# SH6_-_SCIENCE_CONTROLS.net
KiCad netlist of a schematic drawn in Altium Designer
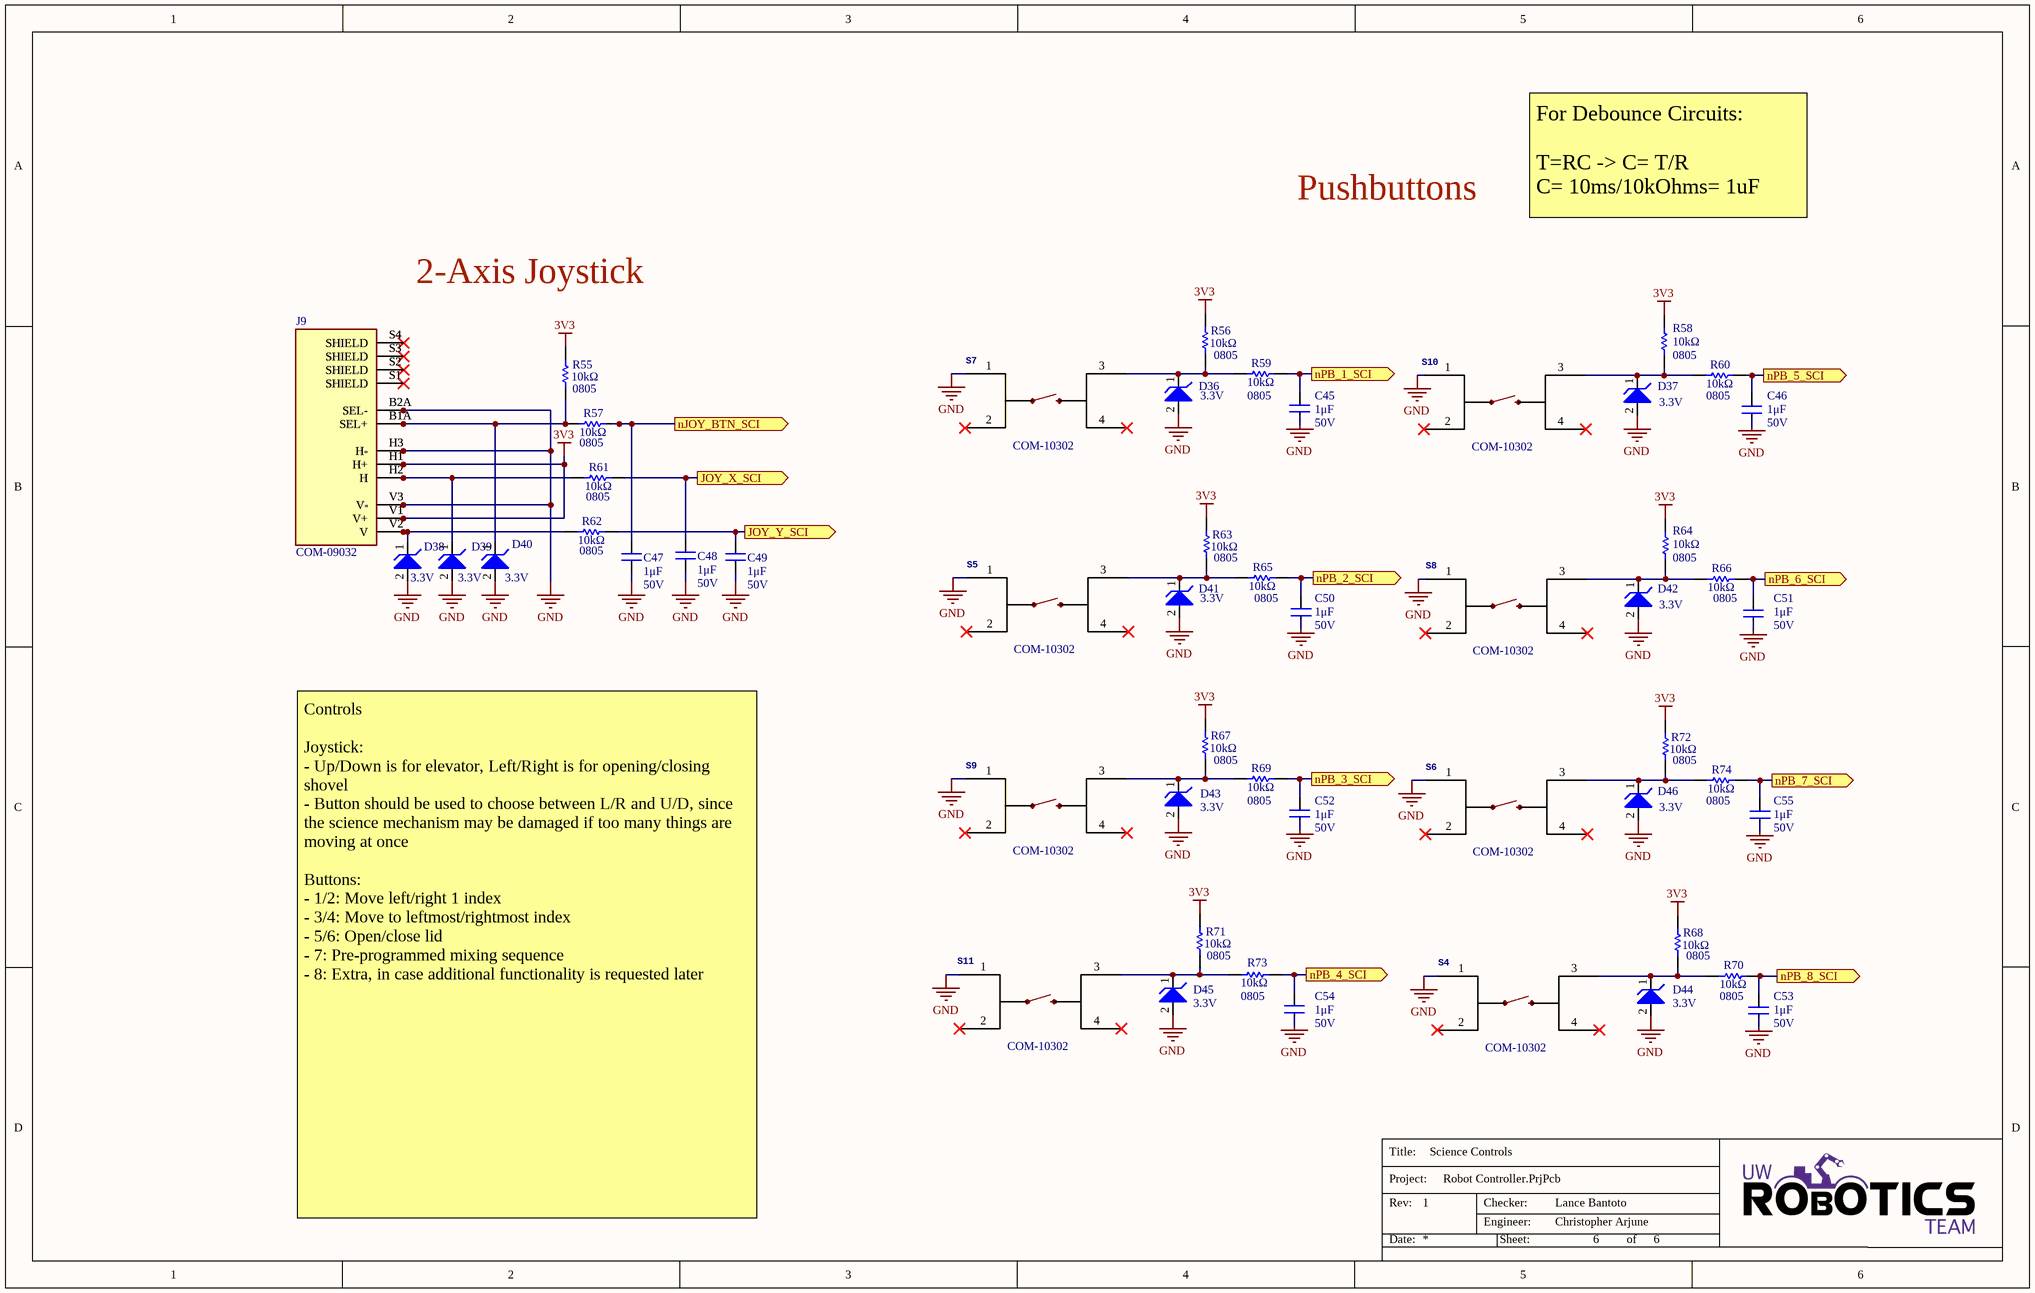
[diagram p0: SH6 - SCIENCE CONTROLS.SchDoc]

(export (version "E")
  (design (tool "Eeschema 10.0.6"))
  (components
    (comp (ref "C45")
      (value "1μF")
      (footprint "CAP2012")
      (description "CAP CER 1UF 50V X7R 0805")
      (fields
        (field (name "VOLTAGE RATING") "50V")
        (field (name "LCSC PART #") "C28323")
        (field (name "Comment") "CAP_1uF_50V_0805")
      )
      (libsource (lib "UWRT_Schematic_Library_2020") (part "CAP_1uF_50V_0805"))
    )
    (comp (ref "C46")
      (value "1μF")
      (footprint "CAP2012")
      (description "CAP CER 1UF 50V X7R 0805")
      (fields
        (field (name "VOLTAGE RATING") "50V")
        (field (name "LCSC PART #") "C28323")
        (field (name "Comment") "CAP_1uF_50V_0805")
      )
      (libsource (lib "UWRT_Schematic_Library_2020") (part "CAP_1uF_50V_0805"))
    )
    (comp (ref "C47")
      (value "1μF")
      (footprint "CAP2012")
      (description "CAP CER 1UF 50V X7R 0805")
      (fields
        (field (name "VOLTAGE RATING") "50V")
        (field (name "LCSC PART #") "C28323")
        (field (name "Comment") "CAP_1uF_50V_0805")
      )
      (libsource (lib "UWRT_Schematic_Library_2020") (part "CAP_1uF_50V_0805"))
    )
    (comp (ref "C48")
      (value "1μF")
      (footprint "CAP2012")
      (description "CAP CER 1UF 50V X7R 0805")
      (fields
        (field (name "VOLTAGE RATING") "50V")
        (field (name "LCSC PART #") "C28323")
        (field (name "Comment") "CAP_1uF_50V_0805")
      )
      (libsource (lib "UWRT_Schematic_Library_2020") (part "CAP_1uF_50V_0805"))
    )
    (comp (ref "C49")
      (value "1μF")
      (footprint "CAP2012")
      (description "CAP CER 1UF 50V X7R 0805")
      (fields
        (field (name "VOLTAGE RATING") "50V")
        (field (name "LCSC PART #") "C28323")
        (field (name "Comment") "CAP_1uF_50V_0805")
      )
      (libsource (lib "UWRT_Schematic_Library_2020") (part "CAP_1uF_50V_0805"))
    )
    (comp (ref "C50")
      (value "1μF")
      (footprint "CAP2012")
      (description "CAP CER 1UF 50V X7R 0805")
      (fields
        (field (name "VOLTAGE RATING") "50V")
        (field (name "LCSC PART #") "C28323")
        (field (name "Comment") "CAP_1uF_50V_0805")
      )
      (libsource (lib "UWRT_Schematic_Library_2020") (part "CAP_1uF_50V_0805"))
    )
    (comp (ref "C51")
      (value "1μF")
      (footprint "CAP2012")
      (description "CAP CER 1UF 50V X7R 0805")
      (fields
        (field (name "VOLTAGE RATING") "50V")
        (field (name "LCSC PART #") "C28323")
        (field (name "Comment") "CAP_1uF_50V_0805")
      )
      (libsource (lib "UWRT_Schematic_Library_2020") (part "CAP_1uF_50V_0805"))
    )
    (comp (ref "C52")
      (value "1μF")
      (footprint "CAP2012")
      (description "CAP CER 1UF 50V X7R 0805")
      (fields
        (field (name "VOLTAGE RATING") "50V")
        (field (name "LCSC PART #") "C28323")
        (field (name "Comment") "CAP_1uF_50V_0805")
      )
      (libsource (lib "UWRT_Schematic_Library_2020") (part "CAP_1uF_50V_0805"))
    )
    (comp (ref "C53")
      (value "1μF")
      (footprint "CAP2012")
      (description "CAP CER 1UF 50V X7R 0805")
      (fields
        (field (name "VOLTAGE RATING") "50V")
        (field (name "LCSC PART #") "C28323")
        (field (name "Comment") "CAP_1uF_50V_0805")
      )
      (libsource (lib "UWRT_Schematic_Library_2020") (part "CAP_1uF_50V_0805"))
    )
    (comp (ref "C54")
      (value "1μF")
      (footprint "CAP2012")
      (description "CAP CER 1UF 50V X7R 0805")
      (fields
        (field (name "VOLTAGE RATING") "50V")
        (field (name "LCSC PART #") "C28323")
        (field (name "Comment") "CAP_1uF_50V_0805")
      )
      (libsource (lib "UWRT_Schematic_Library_2020") (part "CAP_1uF_50V_0805"))
    )
    (comp (ref "C55")
      (value "1μF")
      (footprint "CAP2012")
      (description "CAP CER 1UF 50V X7R 0805")
      (fields
        (field (name "VOLTAGE RATING") "50V")
        (field (name "LCSC PART #") "C28323")
        (field (name "Comment") "CAP_1uF_50V_0805")
      )
      (libsource (lib "UWRT_Schematic_Library_2020") (part "CAP_1uF_50V_0805"))
    )
    (comp (ref "D36")
      (value "TVS_DIODE_UNIDIR_3.3V")
      (description "TVS DIODE 3.3V 14.1V SOD523")
      (fields (field (name "LCSC PART #") "C61148") (field (name "VOLTAGE - REVERSE STANDOFF (TYP)") "3.3V"))
      (libsource (lib "UWRT_Schematic_Library_2020") (part "TVS_DIODE_UNIDIR_3.3V"))
    )
    (comp (ref "D37")
      (value "TVS_DIODE_UNIDIR_3.3V")
      (description "TVS DIODE 3.3V 14.1V SOD523")
      (fields (field (name "LCSC PART #") "C61148") (field (name "VOLTAGE - REVERSE STANDOFF (TYP)") "3.3V"))
      (libsource (lib "UWRT_Schematic_Library_2020") (part "TVS_DIODE_UNIDIR_3.3V"))
    )
    (comp (ref "D38")
      (value "TVS_DIODE_UNIDIR_3.3V")
      (description "TVS DIODE 3.3V 14.1V SOD523")
      (fields (field (name "LCSC PART #") "C61148") (field (name "VOLTAGE - REVERSE STANDOFF (TYP)") "3.3V"))
      (libsource (lib "UWRT_Schematic_Library_2020") (part "TVS_DIODE_UNIDIR_3.3V"))
    )
    (comp (ref "D39")
      (value "TVS_DIODE_UNIDIR_3.3V")
      (description "TVS DIODE 3.3V 14.1V SOD523")
      (fields (field (name "LCSC PART #") "C61148") (field (name "VOLTAGE - REVERSE STANDOFF (TYP)") "3.3V"))
      (libsource (lib "UWRT_Schematic_Library_2020") (part "TVS_DIODE_UNIDIR_3.3V"))
    )
    (comp (ref "D40")
      (value "TVS_DIODE_UNIDIR_3.3V")
      (description "TVS DIODE 3.3V 14.1V SOD523")
      (fields (field (name "LCSC PART #") "C61148") (field (name "VOLTAGE - REVERSE STANDOFF (TYP)") "3.3V"))
      (libsource (lib "UWRT_Schematic_Library_2020") (part "TVS_DIODE_UNIDIR_3.3V"))
    )
    (comp (ref "D41")
      (value "TVS_DIODE_UNIDIR_3.3V")
      (description "TVS DIODE 3.3V 14.1V SOD523")
      (fields (field (name "LCSC PART #") "C61148") (field (name "VOLTAGE - REVERSE STANDOFF (TYP)") "3.3V"))
      (libsource (lib "UWRT_Schematic_Library_2020") (part "TVS_DIODE_UNIDIR_3.3V"))
    )
    (comp (ref "D42")
      (value "TVS_DIODE_UNIDIR_3.3V")
      (description "TVS DIODE 3.3V 14.1V SOD523")
      (fields (field (name "LCSC PART #") "C61148") (field (name "VOLTAGE - REVERSE STANDOFF (TYP)") "3.3V"))
      (libsource (lib "UWRT_Schematic_Library_2020") (part "TVS_DIODE_UNIDIR_3.3V"))
    )
    (comp (ref "D43")
      (value "TVS_DIODE_UNIDIR_3.3V")
      (description "TVS DIODE 3.3V 14.1V SOD523")
      (fields (field (name "LCSC PART #") "C61148") (field (name "VOLTAGE - REVERSE STANDOFF (TYP)") "3.3V"))
      (libsource (lib "UWRT_Schematic_Library_2020") (part "TVS_DIODE_UNIDIR_3.3V"))
    )
    (comp (ref "D44")
      (value "TVS_DIODE_UNIDIR_3.3V")
      (description "TVS DIODE 3.3V 14.1V SOD523")
      (fields (field (name "LCSC PART #") "C61148") (field (name "VOLTAGE - REVERSE STANDOFF (TYP)") "3.3V"))
      (libsource (lib "UWRT_Schematic_Library_2020") (part "TVS_DIODE_UNIDIR_3.3V"))
    )
    (comp (ref "D45")
      (value "TVS_DIODE_UNIDIR_3.3V")
      (description "TVS DIODE 3.3V 14.1V SOD523")
      (fields (field (name "LCSC PART #") "C61148") (field (name "VOLTAGE - REVERSE STANDOFF (TYP)") "3.3V"))
      (libsource (lib "UWRT_Schematic_Library_2020") (part "TVS_DIODE_UNIDIR_3.3V"))
    )
    (comp (ref "D46")
      (value "TVS_DIODE_UNIDIR_3.3V")
      (description "TVS DIODE 3.3V 14.1V SOD523")
      (fields (field (name "LCSC PART #") "C61148") (field (name "VOLTAGE - REVERSE STANDOFF (TYP)") "3.3V"))
      (libsource (lib "UWRT_Schematic_Library_2020") (part "TVS_DIODE_UNIDIR_3.3V"))
    )
    (comp (ref "J9")
      (value "2_AXIS_JOYSTICK")
      (footprint "2_AXIS_JOYSTICK")
      (description "JOYSTICK 10K OHM 2 AXIS TH")
      (fields (field (name "MANUFACTURER PART NUMBER 1") "COM-09032"))
      (libsource (lib "UWRT_Schematic_Library_2020") (part "2_AXIS_JOYSTICK"))
    )
    (comp (ref "R55")
      (value "10kΩ")
      (footprint "RESC0805")
      (description "RES 10K OHM 5% 1/8W 0805")
      (fields
        (field (name "LCSC PART #") "C17414")
        (field (name "PACKAGE/FOOTPRINT") "0805")
        (field (name "Comment") "RES_10kΩ_0805_5%")
      )
      (libsource (lib "UWRT_Schematic_Library_2020") (part "RES_10kΩ_0805_5%"))
    )
    (comp (ref "R56")
      (value "10kΩ")
      (footprint "RESC0805")
      (description "RES 10K OHM 5% 1/8W 0805")
      (fields
        (field (name "LCSC PART #") "C17414")
        (field (name "PACKAGE/FOOTPRINT") "0805")
        (field (name "Comment") "RES_10kΩ_0805_5%")
      )
      (libsource (lib "UWRT_Schematic_Library_2020") (part "RES_10kΩ_0805_5%"))
    )
    (comp (ref "R57")
      (value "10kΩ")
      (footprint "RESC0805")
      (description "RES 10K OHM 5% 1/8W 0805")
      (fields
        (field (name "LCSC PART #") "C17414")
        (field (name "PACKAGE/FOOTPRINT") "0805")
        (field (name "Comment") "RES_10kΩ_0805_5%")
      )
      (libsource (lib "UWRT_Schematic_Library_2020") (part "RES_10kΩ_0805_5%"))
    )
    (comp (ref "R58")
      (value "10kΩ")
      (footprint "RESC0805")
      (description "RES 10K OHM 5% 1/8W 0805")
      (fields
        (field (name "LCSC PART #") "C17414")
        (field (name "PACKAGE/FOOTPRINT") "0805")
        (field (name "Comment") "RES_10kΩ_0805_5%")
      )
      (libsource (lib "UWRT_Schematic_Library_2020") (part "RES_10kΩ_0805_5%"))
    )
    (comp (ref "R59")
      (value "10kΩ")
      (footprint "RESC0805")
      (description "RES 10K OHM 5% 1/8W 0805")
      (fields
        (field (name "LCSC PART #") "C17414")
        (field (name "PACKAGE/FOOTPRINT") "0805")
        (field (name "Comment") "RES_10kΩ_0805_5%")
      )
      (libsource (lib "UWRT_Schematic_Library_2020") (part "RES_10kΩ_0805_5%"))
    )
    (comp (ref "R60")
      (value "10kΩ")
      (footprint "RESC0805")
      (description "RES 10K OHM 5% 1/8W 0805")
      (fields
        (field (name "LCSC PART #") "C17414")
        (field (name "PACKAGE/FOOTPRINT") "0805")
        (field (name "Comment") "RES_10kΩ_0805_5%")
      )
      (libsource (lib "UWRT_Schematic_Library_2020") (part "RES_10kΩ_0805_5%"))
    )
    (comp (ref "R61")
      (value "10kΩ")
      (footprint "RESC0805")
      (description "RES 10K OHM 5% 1/8W 0805")
      (fields
        (field (name "LCSC PART #") "C17414")
        (field (name "PACKAGE/FOOTPRINT") "0805")
        (field (name "Comment") "RES_10kΩ_0805_5%")
      )
      (libsource (lib "UWRT_Schematic_Library_2020") (part "RES_10kΩ_0805_5%"))
    )
    (comp (ref "R62")
      (value "10kΩ")
      (footprint "RESC0805")
      (description "RES 10K OHM 5% 1/8W 0805")
      (fields
        (field (name "LCSC PART #") "C17414")
        (field (name "PACKAGE/FOOTPRINT") "0805")
        (field (name "Comment") "RES_10kΩ_0805_5%")
      )
      (libsource (lib "UWRT_Schematic_Library_2020") (part "RES_10kΩ_0805_5%"))
    )
    (comp (ref "R63")
      (value "10kΩ")
      (footprint "RESC0805")
      (description "RES 10K OHM 5% 1/8W 0805")
      (fields
        (field (name "LCSC PART #") "C17414")
        (field (name "PACKAGE/FOOTPRINT") "0805")
        (field (name "Comment") "RES_10kΩ_0805_5%")
      )
      (libsource (lib "UWRT_Schematic_Library_2020") (part "RES_10kΩ_0805_5%"))
    )
    (comp (ref "R64")
      (value "10kΩ")
      (footprint "RESC0805")
      (description "RES 10K OHM 5% 1/8W 0805")
      (fields
        (field (name "LCSC PART #") "C17414")
        (field (name "PACKAGE/FOOTPRINT") "0805")
        (field (name "Comment") "RES_10kΩ_0805_5%")
      )
      (libsource (lib "UWRT_Schematic_Library_2020") (part "RES_10kΩ_0805_5%"))
    )
    (comp (ref "R65")
      (value "10kΩ")
      (footprint "RESC0805")
      (description "RES 10K OHM 5% 1/8W 0805")
      (fields
        (field (name "LCSC PART #") "C17414")
        (field (name "PACKAGE/FOOTPRINT") "0805")
        (field (name "Comment") "RES_10kΩ_0805_5%")
      )
      (libsource (lib "UWRT_Schematic_Library_2020") (part "RES_10kΩ_0805_5%"))
    )
    (comp (ref "R66")
      (value "10kΩ")
      (footprint "RESC0805")
      (description "RES 10K OHM 5% 1/8W 0805")
      (fields
        (field (name "LCSC PART #") "C17414")
        (field (name "PACKAGE/FOOTPRINT") "0805")
        (field (name "Comment") "RES_10kΩ_0805_5%")
      )
      (libsource (lib "UWRT_Schematic_Library_2020") (part "RES_10kΩ_0805_5%"))
    )
    (comp (ref "R67")
      (value "10kΩ")
      (footprint "RESC0805")
      (description "RES 10K OHM 5% 1/8W 0805")
      (fields
        (field (name "LCSC PART #") "C17414")
        (field (name "PACKAGE/FOOTPRINT") "0805")
        (field (name "Comment") "RES_10kΩ_0805_5%")
      )
      (libsource (lib "UWRT_Schematic_Library_2020") (part "RES_10kΩ_0805_5%"))
    )
    (comp (ref "R68")
      (value "10kΩ")
      (footprint "RESC0805")
      (description "RES 10K OHM 5% 1/8W 0805")
      (fields
        (field (name "LCSC PART #") "C17414")
        (field (name "PACKAGE/FOOTPRINT") "0805")
        (field (name "Comment") "RES_10kΩ_0805_5%")
      )
      (libsource (lib "UWRT_Schematic_Library_2020") (part "RES_10kΩ_0805_5%"))
    )
    (comp (ref "R69")
      (value "10kΩ")
      (footprint "RESC0805")
      (description "RES 10K OHM 5% 1/8W 0805")
      (fields
        (field (name "LCSC PART #") "C17414")
        (field (name "PACKAGE/FOOTPRINT") "0805")
        (field (name "Comment") "RES_10kΩ_0805_5%")
      )
      (libsource (lib "UWRT_Schematic_Library_2020") (part "RES_10kΩ_0805_5%"))
    )
    (comp (ref "R70")
      (value "10kΩ")
      (footprint "RESC0805")
      (description "RES 10K OHM 5% 1/8W 0805")
      (fields
        (field (name "LCSC PART #") "C17414")
        (field (name "PACKAGE/FOOTPRINT") "0805")
        (field (name "Comment") "RES_10kΩ_0805_5%")
      )
      (libsource (lib "UWRT_Schematic_Library_2020") (part "RES_10kΩ_0805_5%"))
    )
    (comp (ref "R71")
      (value "10kΩ")
      (footprint "RESC0805")
      (description "RES 10K OHM 5% 1/8W 0805")
      (fields
        (field (name "LCSC PART #") "C17414")
        (field (name "PACKAGE/FOOTPRINT") "0805")
        (field (name "Comment") "RES_10kΩ_0805_5%")
      )
      (libsource (lib "UWRT_Schematic_Library_2020") (part "RES_10kΩ_0805_5%"))
    )
    (comp (ref "R72")
      (value "10kΩ")
      (footprint "RESC0805")
      (description "RES 10K OHM 5% 1/8W 0805")
      (fields
        (field (name "LCSC PART #") "C17414")
        (field (name "PACKAGE/FOOTPRINT") "0805")
        (field (name "Comment") "RES_10kΩ_0805_5%")
      )
      (libsource (lib "UWRT_Schematic_Library_2020") (part "RES_10kΩ_0805_5%"))
    )
    (comp (ref "R73")
      (value "10kΩ")
      (footprint "RESC0805")
      (description "RES 10K OHM 5% 1/8W 0805")
      (fields
        (field (name "LCSC PART #") "C17414")
        (field (name "PACKAGE/FOOTPRINT") "0805")
        (field (name "Comment") "RES_10kΩ_0805_5%")
      )
      (libsource (lib "UWRT_Schematic_Library_2020") (part "RES_10kΩ_0805_5%"))
    )
    (comp (ref "R74")
      (value "10kΩ")
      (footprint "RESC0805")
      (description "RES 10K OHM 5% 1/8W 0805")
      (fields
        (field (name "LCSC PART #") "C17414")
        (field (name "PACKAGE/FOOTPRINT") "0805")
        (field (name "Comment") "RES_10kΩ_0805_5%")
      )
      (libsource (lib "UWRT_Schematic_Library_2020") (part "RES_10kΩ_0805_5%"))
    )
    (comp (ref "S4")
      (value "SW_MOMENTARY_PUSHBUTTON")
      (footprint "TACTILE_SWITCH_PTH_12MM")
      (description "TACTILE MOMENTARY PUSHBUTTON SPST")
      (fields (field (name "MANUFACTURER PART NUMBER 1") "COM-10302"))
      (libsource (lib "UWRT_Schematic_Library_2020") (part "SW_MOMENTARY_PUSHBUTTON"))
    )
    (comp (ref "S5")
      (value "SW_MOMENTARY_PUSHBUTTON")
      (footprint "TACTILE_SWITCH_PTH_12MM")
      (description "TACTILE MOMENTARY PUSHBUTTON SPST")
      (fields (field (name "MANUFACTURER PART NUMBER 1") "COM-10302"))
      (libsource (lib "UWRT_Schematic_Library_2020") (part "SW_MOMENTARY_PUSHBUTTON"))
    )
    (comp (ref "S6")
      (value "SW_MOMENTARY_PUSHBUTTON")
      (footprint "TACTILE_SWITCH_PTH_12MM")
      (description "TACTILE MOMENTARY PUSHBUTTON SPST")
      (fields (field (name "MANUFACTURER PART NUMBER 1") "COM-10302"))
      (libsource (lib "UWRT_Schematic_Library_2020") (part "SW_MOMENTARY_PUSHBUTTON"))
    )
    (comp (ref "S7")
      (value "SW_MOMENTARY_PUSHBUTTON")
      (footprint "TACTILE_SWITCH_PTH_12MM")
      (description "TACTILE MOMENTARY PUSHBUTTON SPST")
      (fields (field (name "MANUFACTURER PART NUMBER 1") "COM-10302"))
      (libsource (lib "UWRT_Schematic_Library_2020") (part "SW_MOMENTARY_PUSHBUTTON"))
    )
    (comp (ref "S8")
      (value "SW_MOMENTARY_PUSHBUTTON")
      (footprint "TACTILE_SWITCH_PTH_12MM")
      (description "TACTILE MOMENTARY PUSHBUTTON SPST")
      (fields (field (name "MANUFACTURER PART NUMBER 1") "COM-10302"))
      (libsource (lib "UWRT_Schematic_Library_2020") (part "SW_MOMENTARY_PUSHBUTTON"))
    )
    (comp (ref "S9")
      (value "SW_MOMENTARY_PUSHBUTTON")
      (footprint "TACTILE_SWITCH_PTH_12MM")
      (description "TACTILE MOMENTARY PUSHBUTTON SPST")
      (fields (field (name "MANUFACTURER PART NUMBER 1") "COM-10302"))
      (libsource (lib "UWRT_Schematic_Library_2020") (part "SW_MOMENTARY_PUSHBUTTON"))
    )
    (comp (ref "S10")
      (value "SW_MOMENTARY_PUSHBUTTON")
      (footprint "TACTILE_SWITCH_PTH_12MM")
      (description "TACTILE MOMENTARY PUSHBUTTON SPST")
      (fields (field (name "MANUFACTURER PART NUMBER 1") "COM-10302"))
      (libsource (lib "UWRT_Schematic_Library_2020") (part "SW_MOMENTARY_PUSHBUTTON"))
    )
    (comp (ref "S11")
      (value "SW_MOMENTARY_PUSHBUTTON")
      (footprint "TACTILE_SWITCH_PTH_12MM")
      (description "TACTILE MOMENTARY PUSHBUTTON SPST")
      (fields (field (name "MANUFACTURER PART NUMBER 1") "COM-10302"))
      (libsource (lib "UWRT_Schematic_Library_2020") (part "SW_MOMENTARY_PUSHBUTTON"))
    )
  )
  (nets
    (net (code "1") (name "/JOY_X_SCI") (class "Default")
      (node (ref "C48") (pin "2") (pinfunction "2_2") (pintype "passive"))
      (node (ref "R61") (pin "2") (pinfunction "2_2") (pintype "passive"))
    )
    (net (code "2") (name "/JOY_Y_SCI") (class "Default")
      (node (ref "C49") (pin "2") (pinfunction "2_2") (pintype "passive"))
      (node (ref "R62") (pin "2") (pinfunction "2_2") (pintype "passive"))
    )
    (net (code "3") (name "/nJOY_BTN_SCI") (class "Default")
      (node (ref "C47") (pin "2") (pinfunction "2_2") (pintype "passive"))
      (node (ref "R57") (pin "2") (pinfunction "2_2") (pintype "passive"))
    )
    (net (code "4") (name "/nPB_1_SCI") (class "Default")
      (node (ref "C45") (pin "2") (pinfunction "2_2") (pintype "passive"))
      (node (ref "R59") (pin "2") (pinfunction "2_2") (pintype "passive"))
    )
    (net (code "5") (name "/nPB_2_SCI") (class "Default")
      (node (ref "C50") (pin "2") (pinfunction "2_2") (pintype "passive"))
      (node (ref "R65") (pin "2") (pinfunction "2_2") (pintype "passive"))
    )
    (net (code "6") (name "/nPB_3_SCI") (class "Default")
      (node (ref "C52") (pin "2") (pinfunction "2_2") (pintype "passive"))
      (node (ref "R69") (pin "2") (pinfunction "2_2") (pintype "passive"))
    )
    (net (code "7") (name "/nPB_4_SCI") (class "Default")
      (node (ref "C54") (pin "2") (pinfunction "2_2") (pintype "passive"))
      (node (ref "R73") (pin "2") (pinfunction "2_2") (pintype "passive"))
    )
    (net (code "8") (name "/nPB_5_SCI") (class "Default")
      (node (ref "C46") (pin "2") (pinfunction "2_2") (pintype "passive"))
      (node (ref "R60") (pin "2") (pinfunction "2_2") (pintype "passive"))
    )
    (net (code "9") (name "/nPB_6_SCI") (class "Default")
      (node (ref "C51") (pin "2") (pinfunction "2_2") (pintype "passive"))
      (node (ref "R66") (pin "2") (pinfunction "2_2") (pintype "passive"))
    )
    (net (code "10") (name "/nPB_7_SCI") (class "Default")
      (node (ref "C55") (pin "2") (pinfunction "2_2") (pintype "passive"))
      (node (ref "R74") (pin "2") (pinfunction "2_2") (pintype "passive"))
    )
    (net (code "11") (name "/nPB_8_SCI") (class "Default")
      (node (ref "C53") (pin "2") (pinfunction "2_2") (pintype "passive"))
      (node (ref "R70") (pin "2") (pinfunction "2_2") (pintype "passive"))
    )
    (net (code "12") (name "3V3") (class "Default")
      (node (ref "J9") (pin "H1") (pinfunction "H+_H1") (pintype "passive"))
      (node (ref "J9") (pin "V1") (pinfunction "V+_V1") (pintype "passive"))
      (node (ref "R55") (pin "1") (pinfunction "1_1") (pintype "passive"))
      (node (ref "R56") (pin "1") (pinfunction "1_1") (pintype "passive"))
      (node (ref "R58") (pin "1") (pinfunction "1_1") (pintype "passive"))
      (node (ref "R63") (pin "1") (pinfunction "1_1") (pintype "passive"))
      (node (ref "R64") (pin "1") (pinfunction "1_1") (pintype "passive"))
      (node (ref "R67") (pin "1") (pinfunction "1_1") (pintype "passive"))
      (node (ref "R68") (pin "1") (pinfunction "1_1") (pintype "passive"))
      (node (ref "R71") (pin "1") (pinfunction "1_1") (pintype "passive"))
      (node (ref "R72") (pin "1") (pinfunction "1_1") (pintype "passive"))
    )
    (net (code "13") (name "GND") (class "Default")
      (node (ref "C45") (pin "1") (pinfunction "1_1") (pintype "passive"))
      (node (ref "C46") (pin "1") (pinfunction "1_1") (pintype "passive"))
      (node (ref "C47") (pin "1") (pinfunction "1_1") (pintype "passive"))
      (node (ref "C48") (pin "1") (pinfunction "1_1") (pintype "passive"))
      (node (ref "C49") (pin "1") (pinfunction "1_1") (pintype "passive"))
      (node (ref "C50") (pin "1") (pinfunction "1_1") (pintype "passive"))
      (node (ref "C51") (pin "1") (pinfunction "1_1") (pintype "passive"))
      (node (ref "C52") (pin "1") (pinfunction "1_1") (pintype "passive"))
      (node (ref "C53") (pin "1") (pinfunction "1_1") (pintype "passive"))
      (node (ref "C54") (pin "1") (pinfunction "1_1") (pintype "passive"))
      (node (ref "C55") (pin "1") (pinfunction "1_1") (pintype "passive"))
      (node (ref "D36") (pin "2") (pinfunction "2_2") (pintype "passive"))
      (node (ref "D37") (pin "2") (pinfunction "2_2") (pintype "passive"))
      (node (ref "D38") (pin "2") (pinfunction "2_2") (pintype "passive"))
      (node (ref "D39") (pin "2") (pinfunction "2_2") (pintype "passive"))
      (node (ref "D40") (pin "2") (pinfunction "2_2") (pintype "passive"))
      (node (ref "D41") (pin "2") (pinfunction "2_2") (pintype "passive"))
      (node (ref "D42") (pin "2") (pinfunction "2_2") (pintype "passive"))
      (node (ref "D43") (pin "2") (pinfunction "2_2") (pintype "passive"))
      (node (ref "D44") (pin "2") (pinfunction "2_2") (pintype "passive"))
      (node (ref "D45") (pin "2") (pinfunction "2_2") (pintype "passive"))
      (node (ref "D46") (pin "2") (pinfunction "2_2") (pintype "passive"))
      (node (ref "J9") (pin "B2A") (pinfunction "SEL-_B2A") (pintype "passive"))
      (node (ref "J9") (pin "H3") (pinfunction "H-_H3") (pintype "passive"))
      (node (ref "J9") (pin "V3") (pinfunction "V-_V3") (pintype "passive"))
      (node (ref "S10") (pin "1") (pinfunction "1_1") (pintype "passive"))
      (node (ref "S11") (pin "1") (pinfunction "1_1") (pintype "passive"))
      (node (ref "S4") (pin "1") (pinfunction "1_1") (pintype "passive"))
      (node (ref "S5") (pin "1") (pinfunction "1_1") (pintype "passive"))
      (node (ref "S6") (pin "1") (pinfunction "1_1") (pintype "passive"))
      (node (ref "S7") (pin "1") (pinfunction "1_1") (pintype "passive"))
      (node (ref "S8") (pin "1") (pinfunction "1_1") (pintype "passive"))
      (node (ref "S9") (pin "1") (pinfunction "1_1") (pintype "passive"))
    )
    (net (code "14") (name "Net-(D36-Pad1)") (class "Default")
      (node (ref "D36") (pin "1") (pinfunction "1_1") (pintype "passive"))
      (node (ref "R56") (pin "2") (pinfunction "2_2") (pintype "passive"))
      (node (ref "R59") (pin "1") (pinfunction "1_1") (pintype "passive"))
      (node (ref "S7") (pin "3") (pinfunction "3_3") (pintype "passive"))
    )
    (net (code "15") (name "Net-(D37-Pad1)") (class "Default")
      (node (ref "D37") (pin "1") (pinfunction "1_1") (pintype "passive"))
      (node (ref "R58") (pin "2") (pinfunction "2_2") (pintype "passive"))
      (node (ref "R60") (pin "1") (pinfunction "1_1") (pintype "passive"))
      (node (ref "S10") (pin "3") (pinfunction "3_3") (pintype "passive"))
    )
    (net (code "16") (name "Net-(D41-Pad1)") (class "Default")
      (node (ref "D41") (pin "1") (pinfunction "1_1") (pintype "passive"))
      (node (ref "R63") (pin "2") (pinfunction "2_2") (pintype "passive"))
      (node (ref "R65") (pin "1") (pinfunction "1_1") (pintype "passive"))
      (node (ref "S5") (pin "3") (pinfunction "3_3") (pintype "passive"))
    )
    (net (code "17") (name "Net-(D42-Pad1)") (class "Default")
      (node (ref "D42") (pin "1") (pinfunction "1_1") (pintype "passive"))
      (node (ref "R64") (pin "2") (pinfunction "2_2") (pintype "passive"))
      (node (ref "R66") (pin "1") (pinfunction "1_1") (pintype "passive"))
      (node (ref "S8") (pin "3") (pinfunction "3_3") (pintype "passive"))
    )
    (net (code "18") (name "Net-(D43-Pad1)") (class "Default")
      (node (ref "D43") (pin "1") (pinfunction "1_1") (pintype "passive"))
      (node (ref "R67") (pin "2") (pinfunction "2_2") (pintype "passive"))
      (node (ref "R69") (pin "1") (pinfunction "1_1") (pintype "passive"))
      (node (ref "S9") (pin "3") (pinfunction "3_3") (pintype "passive"))
    )
    (net (code "19") (name "Net-(D44-Pad1)") (class "Default")
      (node (ref "D44") (pin "1") (pinfunction "1_1") (pintype "passive"))
      (node (ref "R68") (pin "2") (pinfunction "2_2") (pintype "passive"))
      (node (ref "R70") (pin "1") (pinfunction "1_1") (pintype "passive"))
      (node (ref "S4") (pin "3") (pinfunction "3_3") (pintype "passive"))
    )
    (net (code "20") (name "Net-(D45-Pad1)") (class "Default")
      (node (ref "D45") (pin "1") (pinfunction "1_1") (pintype "passive"))
      (node (ref "R71") (pin "2") (pinfunction "2_2") (pintype "passive"))
      (node (ref "R73") (pin "1") (pinfunction "1_1") (pintype "passive"))
      (node (ref "S11") (pin "3") (pinfunction "3_3") (pintype "passive"))
    )
    (net (code "21") (name "Net-(D46-Pad1)") (class "Default")
      (node (ref "D46") (pin "1") (pinfunction "1_1") (pintype "passive"))
      (node (ref "R72") (pin "2") (pinfunction "2_2") (pintype "passive"))
      (node (ref "R74") (pin "1") (pinfunction "1_1") (pintype "passive"))
      (node (ref "S6") (pin "3") (pinfunction "3_3") (pintype "passive"))
    )
    (net (code "22") (name "Net-(J9-H)") (class "Default")
      (node (ref "D39") (pin "1") (pinfunction "1_1") (pintype "passive"))
      (node (ref "J9") (pin "H2") (pinfunction "H_H2") (pintype "passive"))
      (node (ref "R61") (pin "1") (pinfunction "1_1") (pintype "passive"))
    )
    (net (code "23") (name "Net-(J9-SEL+)") (class "Default")
      (node (ref "D40") (pin "1") (pinfunction "1_1") (pintype "passive"))
      (node (ref "J9") (pin "B1A") (pinfunction "SEL+_B1A") (pintype "passive"))
      (node (ref "R55") (pin "2") (pinfunction "2_2") (pintype "passive"))
      (node (ref "R57") (pin "1") (pinfunction "1_1") (pintype "passive"))
    )
    (net (code "24") (name "Net-(J9-V)") (class "Default")
      (node (ref "D38") (pin "1") (pinfunction "1_1") (pintype "passive"))
      (node (ref "J9") (pin "V2") (pinfunction "V_V2") (pintype "passive"))
      (node (ref "R62") (pin "1") (pinfunction "1_1") (pintype "passive"))
    )
    (net (code "25") (name "unconnected-(J9-SHIELD-PadS1)") (class "Default")
      (node (ref "J9") (pin "S1") (pinfunction "SHIELD_S1") (pintype "passive+no_connect"))
    )
    (net (code "26") (name "unconnected-(J9-SHIELD-PadS2)") (class "Default")
      (node (ref "J9") (pin "S2") (pinfunction "SHIELD_S2") (pintype "passive+no_connect"))
    )
    (net (code "27") (name "unconnected-(J9-SHIELD-PadS3)") (class "Default")
      (node (ref "J9") (pin "S3") (pinfunction "SHIELD_S3") (pintype "passive+no_connect"))
    )
    (net (code "28") (name "unconnected-(J9-SHIELD-PadS4)") (class "Default")
      (node (ref "J9") (pin "S4") (pinfunction "SHIELD_S4") (pintype "passive+no_connect"))
    )
    (net (code "29") (name "unconnected-(S4-Pad2)") (class "Default")
      (node (ref "S4") (pin "2") (pinfunction "2_2") (pintype "passive+no_connect"))
    )
    (net (code "30") (name "unconnected-(S4-Pad4)") (class "Default")
      (node (ref "S4") (pin "4") (pinfunction "4_4") (pintype "passive+no_connect"))
    )
    (net (code "31") (name "unconnected-(S5-Pad2)") (class "Default")
      (node (ref "S5") (pin "2") (pinfunction "2_2") (pintype "passive+no_connect"))
    )
    (net (code "32") (name "unconnected-(S5-Pad4)") (class "Default")
      (node (ref "S5") (pin "4") (pinfunction "4_4") (pintype "passive+no_connect"))
    )
    (net (code "33") (name "unconnected-(S6-Pad2)") (class "Default")
      (node (ref "S6") (pin "2") (pinfunction "2_2") (pintype "passive+no_connect"))
    )
    (net (code "34") (name "unconnected-(S6-Pad4)") (class "Default")
      (node (ref "S6") (pin "4") (pinfunction "4_4") (pintype "passive+no_connect"))
    )
    (net (code "35") (name "unconnected-(S7-Pad2)") (class "Default")
      (node (ref "S7") (pin "2") (pinfunction "2_2") (pintype "passive+no_connect"))
    )
    (net (code "36") (name "unconnected-(S7-Pad4)") (class "Default")
      (node (ref "S7") (pin "4") (pinfunction "4_4") (pintype "passive+no_connect"))
    )
    (net (code "37") (name "unconnected-(S8-Pad2)") (class "Default")
      (node (ref "S8") (pin "2") (pinfunction "2_2") (pintype "passive+no_connect"))
    )
    (net (code "38") (name "unconnected-(S8-Pad4)") (class "Default")
      (node (ref "S8") (pin "4") (pinfunction "4_4") (pintype "passive+no_connect"))
    )
    (net (code "39") (name "unconnected-(S9-Pad2)") (class "Default")
      (node (ref "S9") (pin "2") (pinfunction "2_2") (pintype "passive+no_connect"))
    )
    (net (code "40") (name "unconnected-(S9-Pad4)") (class "Default")
      (node (ref "S9") (pin "4") (pinfunction "4_4") (pintype "passive+no_connect"))
    )
    (net (code "41") (name "unconnected-(S10-Pad2)") (class "Default")
      (node (ref "S10") (pin "2") (pinfunction "2_2") (pintype "passive+no_connect"))
    )
    (net (code "42") (name "unconnected-(S10-Pad4)") (class "Default")
      (node (ref "S10") (pin "4") (pinfunction "4_4") (pintype "passive+no_connect"))
    )
    (net (code "43") (name "unconnected-(S11-Pad2)") (class "Default")
      (node (ref "S11") (pin "2") (pinfunction "2_2") (pintype "passive+no_connect"))
    )
    (net (code "44") (name "unconnected-(S11-Pad4)") (class "Default")
      (node (ref "S11") (pin "4") (pinfunction "4_4") (pintype "passive+no_connect"))
    )
  )
)
